# FPGA_POWER_AND_CONFIGURATION.net
KiCad netlist of a schematic drawn in Altium Designer
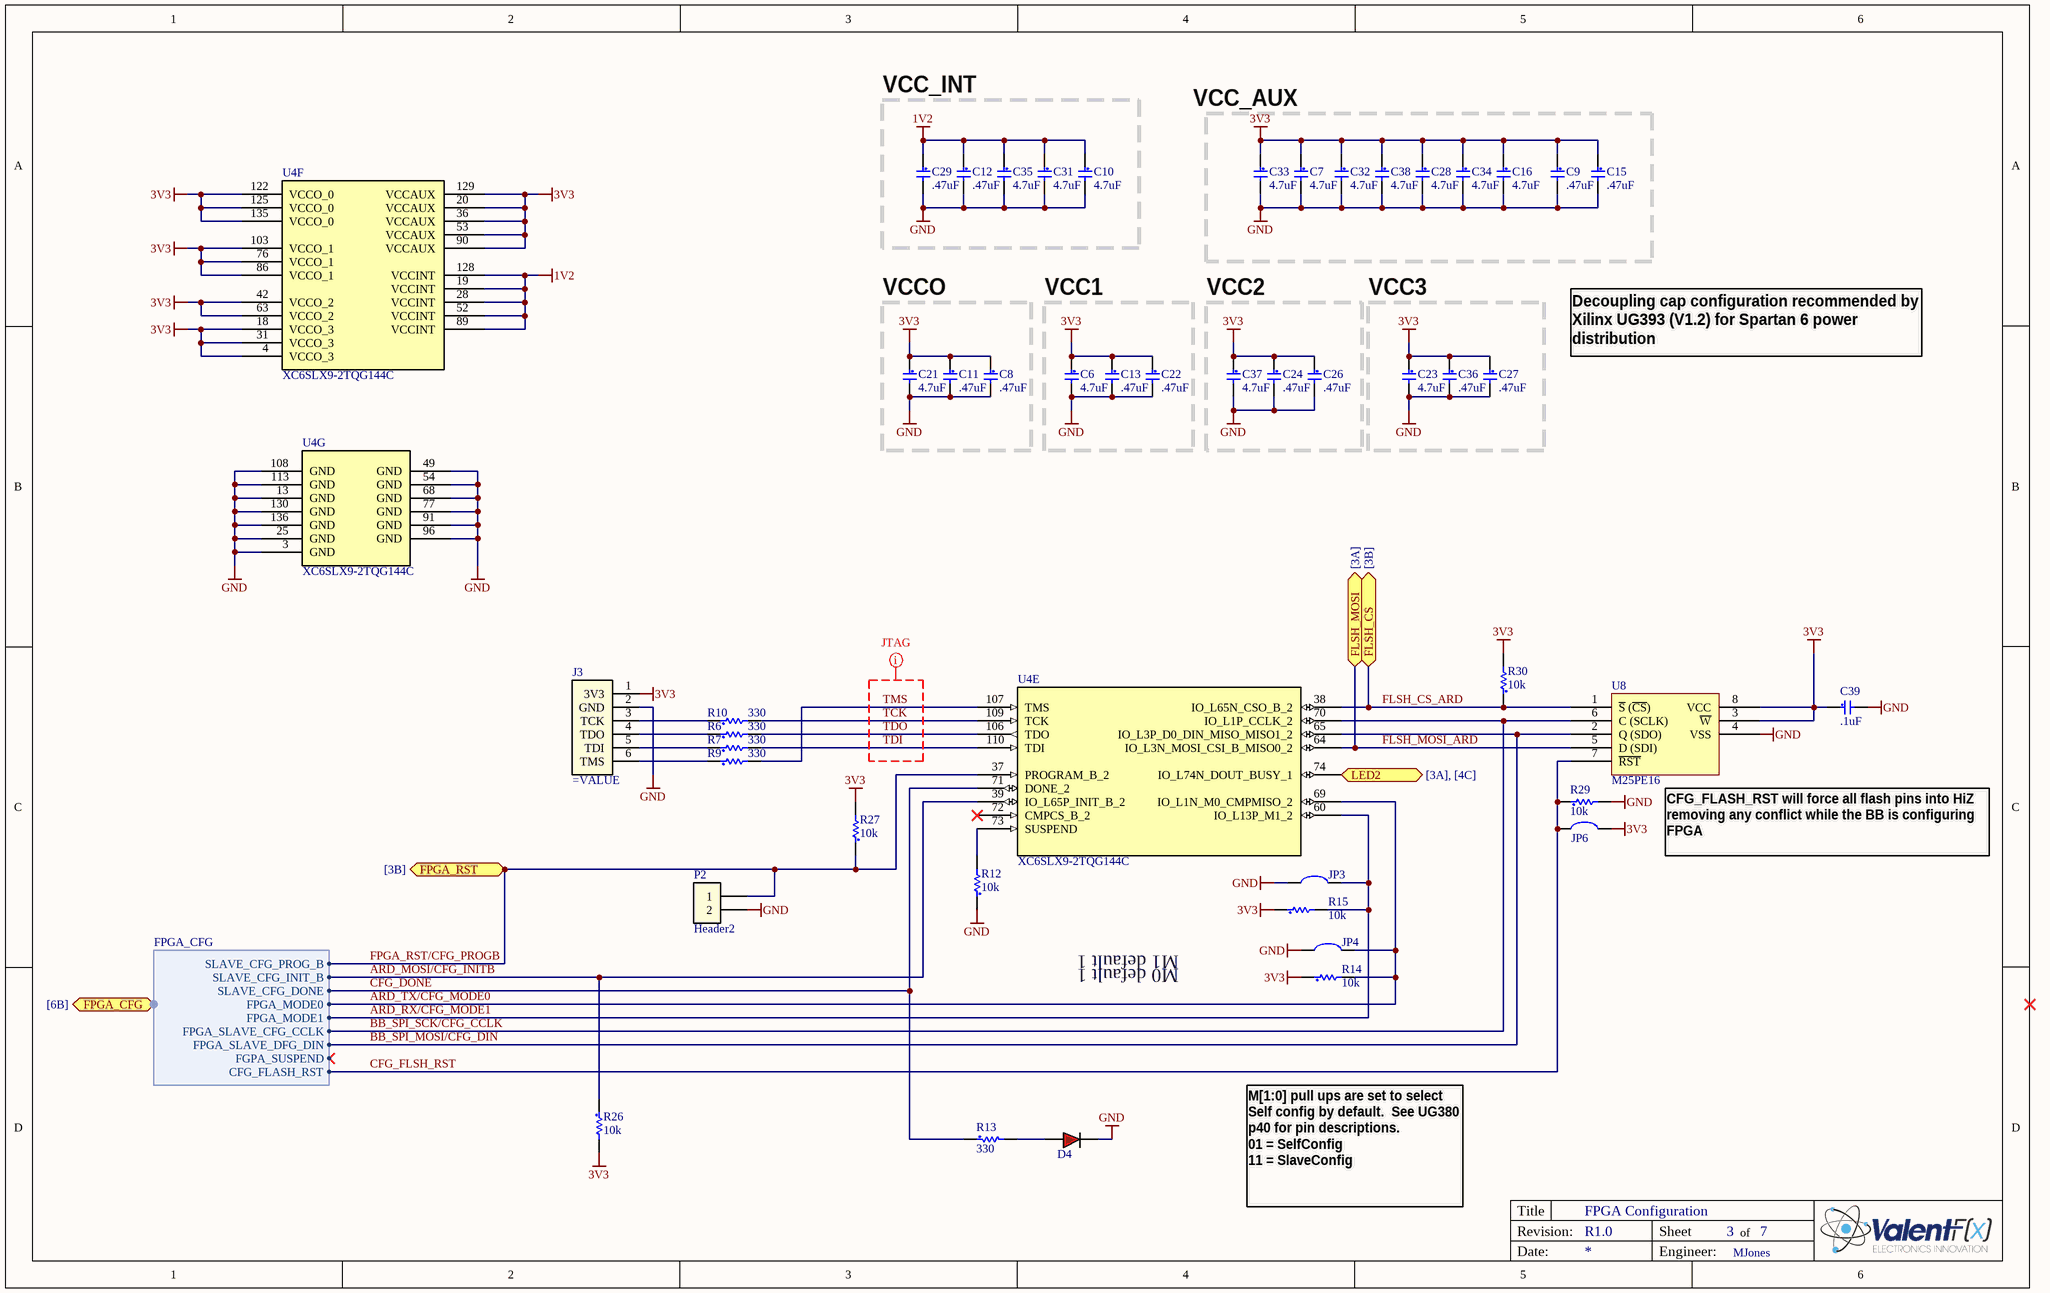
[diagram p0: FPGA_POWER_AND_CONFIGURATION.SchDoc]

(export (version "E")
  (design (tool "Eeschema 10.0.6"))
  (components
    (comp (ref "C6")
      (value "4.7uF")
      (footprint "C0603 - Marked")
      (description "4.7uF 6.3volts X5R 10% (MLCC) - SMD/SMT 0603")
      (fields
        (field (name "MANUFACTURER") "Murata Electronics North America")
        (field (name "MANUFACTURER PART NUMBER") "GRM188R60J475KE19D")
      )
      (libsource (lib "mCapacitors") (part "C0603 - GRM188R60J475KE19D"))
    )
    (comp (ref "C7")
      (value "4.7uF")
      (footprint "C0603 - Marked")
      (description "4.7uF 6.3volts X5R 10% (MLCC) - SMD/SMT 0603")
      (fields
        (field (name "MANUFACTURER") "Murata Electronics North America")
        (field (name "MANUFACTURER PART NUMBER") "GRM188R60J475KE19D")
      )
      (libsource (lib "mCapacitors") (part "C0603 - GRM188R60J475KE19D"))
    )
    (comp (ref "C8")
      (value ".47uF")
      (footprint "mRCL:C0603")
      (description ".47uF 25VDC X7R 10% SMD 0603 Paper T/R CERAMIC")
      (fields
        (field (name "MANUFACTURER") "Murata Electronics North America")
        (field (name "MANUFACTURER PART NUMBER") "GCM188R71E474KA64D")
      )
      (libsource (lib "mCapacitors") (part "C0603 - GCM188R71E474KA64D"))
    )
    (comp (ref "C9")
      (value ".47uF")
      (footprint "mRCL:C0603")
      (description ".47uF 25VDC X7R 10% SMD 0603 Paper T/R CERAMIC")
      (fields
        (field (name "MANUFACTURER") "Murata Electronics North America")
        (field (name "MANUFACTURER PART NUMBER") "GCM188R71E474KA64D")
      )
      (libsource (lib "mCapacitors") (part "C0603 - GCM188R71E474KA64D"))
    )
    (comp (ref "C10")
      (value "4.7uF")
      (footprint "C0603 - Marked")
      (description "4.7uF 6.3volts X5R 10% (MLCC) - SMD/SMT 0603")
      (fields
        (field (name "MANUFACTURER") "Murata Electronics North America")
        (field (name "MANUFACTURER PART NUMBER") "GRM188R60J475KE19D")
      )
      (libsource (lib "mCapacitors") (part "C0603 - GRM188R60J475KE19D"))
    )
    (comp (ref "C11")
      (value ".47uF")
      (footprint "mRCL:C0603")
      (description ".47uF 25VDC X7R 10% SMD 0603 Paper T/R CERAMIC")
      (fields
        (field (name "MANUFACTURER") "Murata Electronics North America")
        (field (name "MANUFACTURER PART NUMBER") "GCM188R71E474KA64D")
      )
      (libsource (lib "mCapacitors") (part "C0603 - GCM188R71E474KA64D"))
    )
    (comp (ref "C12")
      (value ".47uF")
      (footprint "mRCL:C0603")
      (description ".47uF 25VDC X7R 10% SMD 0603 Paper T/R CERAMIC")
      (fields
        (field (name "MANUFACTURER") "Murata Electronics North America")
        (field (name "MANUFACTURER PART NUMBER") "GCM188R71E474KA64D")
      )
      (libsource (lib "mCapacitors") (part "C0603 - GCM188R71E474KA64D"))
    )
    (comp (ref "C13")
      (value ".47uF")
      (footprint "mRCL:C0603")
      (description ".47uF 25VDC X7R 10% SMD 0603 Paper T/R CERAMIC")
      (fields
        (field (name "MANUFACTURER") "Murata Electronics North America")
        (field (name "MANUFACTURER PART NUMBER") "GCM188R71E474KA64D")
      )
      (libsource (lib "mCapacitors") (part "C0603 - GCM188R71E474KA64D"))
    )
    (comp (ref "C15")
      (value ".47uF")
      (footprint "mRCL:C0603")
      (description ".47uF 25VDC X7R 10% SMD 0603 Paper T/R CERAMIC")
      (fields
        (field (name "MANUFACTURER") "Murata Electronics North America")
        (field (name "MANUFACTURER PART NUMBER") "GCM188R71E474KA64D")
      )
      (libsource (lib "mCapacitors") (part "C0603 - GCM188R71E474KA64D"))
    )
    (comp (ref "C16")
      (value "4.7uF")
      (footprint "C0603 - Marked")
      (description "4.7uF 6.3volts X5R 10% (MLCC) - SMD/SMT 0603")
      (fields
        (field (name "MANUFACTURER") "Murata Electronics North America")
        (field (name "MANUFACTURER PART NUMBER") "GRM188R60J475KE19D")
      )
      (libsource (lib "mCapacitors") (part "C0603 - GRM188R60J475KE19D"))
    )
    (comp (ref "C21")
      (value "4.7uF")
      (footprint "C0603 - Marked")
      (description "4.7uF 6.3volts X5R 10% (MLCC) - SMD/SMT 0603")
      (fields
        (field (name "MANUFACTURER") "Murata Electronics North America")
        (field (name "MANUFACTURER PART NUMBER") "GRM188R60J475KE19D")
      )
      (libsource (lib "mCapacitors") (part "C0603 - GRM188R60J475KE19D"))
    )
    (comp (ref "C22")
      (value ".47uF")
      (footprint "mRCL:C0603")
      (description ".47uF 25VDC X7R 10% SMD 0603 Paper T/R CERAMIC")
      (fields
        (field (name "MANUFACTURER") "Murata Electronics North America")
        (field (name "MANUFACTURER PART NUMBER") "GCM188R71E474KA64D")
      )
      (libsource (lib "mCapacitors") (part "C0603 - GCM188R71E474KA64D"))
    )
    (comp (ref "C23")
      (value "4.7uF")
      (footprint "C0603 - Marked")
      (description "4.7uF 6.3volts X5R 10% (MLCC) - SMD/SMT 0603")
      (fields
        (field (name "MANUFACTURER") "Murata Electronics North America")
        (field (name "MANUFACTURER PART NUMBER") "GRM188R60J475KE19D")
      )
      (libsource (lib "mCapacitors") (part "C0603 - GRM188R60J475KE19D"))
    )
    (comp (ref "C24")
      (value ".47uF")
      (footprint "mRCL:C0603")
      (description ".47uF 25VDC X7R 10% SMD 0603 Paper T/R CERAMIC")
      (fields
        (field (name "MANUFACTURER") "Murata Electronics North America")
        (field (name "MANUFACTURER PART NUMBER") "GCM188R71E474KA64D")
      )
      (libsource (lib "mCapacitors") (part "C0603 - GCM188R71E474KA64D"))
    )
    (comp (ref "C26")
      (value ".47uF")
      (footprint "mRCL:C0603")
      (description ".47uF 25VDC X7R 10% SMD 0603 Paper T/R CERAMIC")
      (fields
        (field (name "MANUFACTURER") "Murata Electronics North America")
        (field (name "MANUFACTURER PART NUMBER") "GCM188R71E474KA64D")
      )
      (libsource (lib "mCapacitors") (part "C0603 - GCM188R71E474KA64D"))
    )
    (comp (ref "C27")
      (value ".47uF")
      (footprint "mRCL:C0603")
      (description ".47uF 25VDC X7R 10% SMD 0603 Paper T/R CERAMIC")
      (fields
        (field (name "MANUFACTURER") "Murata Electronics North America")
        (field (name "MANUFACTURER PART NUMBER") "GCM188R71E474KA64D")
      )
      (libsource (lib "mCapacitors") (part "C0603 - GCM188R71E474KA64D"))
    )
    (comp (ref "C28")
      (value "4.7uF")
      (footprint "C0603 - Marked")
      (description "4.7uF 6.3volts X5R 10% (MLCC) - SMD/SMT 0603")
      (fields
        (field (name "MANUFACTURER") "Murata Electronics North America")
        (field (name "MANUFACTURER PART NUMBER") "GRM188R60J475KE19D")
      )
      (libsource (lib "mCapacitors") (part "C0603 - GRM188R60J475KE19D"))
    )
    (comp (ref "C29")
      (value ".47uF")
      (footprint "mRCL:C0603")
      (description ".47uF 25VDC X7R 10% SMD 0603 Paper T/R CERAMIC")
      (fields
        (field (name "MANUFACTURER") "Murata Electronics North America")
        (field (name "MANUFACTURER PART NUMBER") "GCM188R71E474KA64D")
      )
      (libsource (lib "mCapacitors") (part "C0603 - GCM188R71E474KA64D"))
    )
    (comp (ref "C31")
      (value "4.7uF")
      (footprint "C0603 - Marked")
      (description "4.7uF 6.3volts X5R 10% (MLCC) - SMD/SMT 0603")
      (fields
        (field (name "MANUFACTURER") "Murata Electronics North America")
        (field (name "MANUFACTURER PART NUMBER") "GRM188R60J475KE19D")
      )
      (libsource (lib "mCapacitors") (part "C0603 - GRM188R60J475KE19D"))
    )
    (comp (ref "C32")
      (value "4.7uF")
      (footprint "C0603 - Marked")
      (description "4.7uF 6.3volts X5R 10% (MLCC) - SMD/SMT 0603")
      (fields
        (field (name "MANUFACTURER") "Murata Electronics North America")
        (field (name "MANUFACTURER PART NUMBER") "GRM188R60J475KE19D")
      )
      (libsource (lib "mCapacitors") (part "C0603 - GRM188R60J475KE19D"))
    )
    (comp (ref "C33")
      (value "4.7uF")
      (footprint "C0603 - Marked")
      (description "4.7uF 6.3volts X5R 10% (MLCC) - SMD/SMT 0603")
      (fields
        (field (name "MANUFACTURER") "Murata Electronics North America")
        (field (name "MANUFACTURER PART NUMBER") "GRM188R60J475KE19D")
      )
      (libsource (lib "mCapacitors") (part "C0603 - GRM188R60J475KE19D"))
    )
    (comp (ref "C34")
      (value "4.7uF")
      (footprint "C0603 - Marked")
      (description "4.7uF 6.3volts X5R 10% (MLCC) - SMD/SMT 0603")
      (fields
        (field (name "MANUFACTURER") "Murata Electronics North America")
        (field (name "MANUFACTURER PART NUMBER") "GRM188R60J475KE19D")
      )
      (libsource (lib "mCapacitors") (part "C0603 - GRM188R60J475KE19D"))
    )
    (comp (ref "C35")
      (value "4.7uF")
      (footprint "C0603 - Marked")
      (description "4.7uF 6.3volts X5R 10% (MLCC) - SMD/SMT 0603")
      (fields
        (field (name "MANUFACTURER") "Murata Electronics North America")
        (field (name "MANUFACTURER PART NUMBER") "GRM188R60J475KE19D")
      )
      (libsource (lib "mCapacitors") (part "C0603 - GRM188R60J475KE19D"))
    )
    (comp (ref "C36")
      (value ".47uF")
      (footprint "mRCL:C0603")
      (description ".47uF 25VDC X7R 10% SMD 0603 Paper T/R CERAMIC")
      (fields
        (field (name "MANUFACTURER") "Murata Electronics North America")
        (field (name "MANUFACTURER PART NUMBER") "GCM188R71E474KA64D")
      )
      (libsource (lib "mCapacitors") (part "C0603 - GCM188R71E474KA64D"))
    )
    (comp (ref "C37")
      (value "4.7uF")
      (footprint "C0603 - Marked")
      (description "4.7uF 6.3volts X5R 10% (MLCC) - SMD/SMT 0603")
      (fields
        (field (name "MANUFACTURER") "Murata Electronics North America")
        (field (name "MANUFACTURER PART NUMBER") "GRM188R60J475KE19D")
      )
      (libsource (lib "mCapacitors") (part "C0603 - GRM188R60J475KE19D"))
    )
    (comp (ref "C38")
      (value "4.7uF")
      (footprint "C0603 - Marked")
      (description "4.7uF 6.3volts X5R 10% (MLCC) - SMD/SMT 0603")
      (fields
        (field (name "MANUFACTURER") "Murata Electronics North America")
        (field (name "MANUFACTURER PART NUMBER") "GRM188R60J475KE19D")
      )
      (libsource (lib "mCapacitors") (part "C0603 - GRM188R60J475KE19D"))
    )
    (comp (ref "C39")
      (value ".1uF")
      (footprint "c0603")
      (description "CAP CER 0.1UF 25V Y5V 0603")
      (fields
        (field (name "MANUFACTURER") "Samsung Electro-Mechanics America, Inc")
        (field (name "MANUFACTURER PART NUMBER") "CL10F104ZA8NNNC")
      )
      (libsource (lib "mCapacitors") (part "C0603 - CL10F104ZA8NNNC"))
    )
    (comp (ref "D4")
      (value "598-8010-107F")
      (footprint "LED_0603 - RED")
      (description "LED ALINGAP RED CLEAR 0603 SMD")
      (fields (field (name "MANUFACTURER") "Dialight"))
      (libsource (lib "mDiode") (part "LED0603 - 598-8010-107F"))
    )
    (comp (ref "J3")
      (value "~")
      (footprint "JTAG - Digilent HS1 RA")
      (description "DIGILENT - 410-205 - PROGRAMMING CABLE, JTAG HS1, USB2")
      (fields
        (field (name "MANUFACTURER") "Samtec")
        (field (name "MANUFACTURER PART NUMBER") "TSW-106-08-G-S-RA")
      )
      (libsource (lib "mConnector") (part "JTAG - Digilent HS1"))
    )
    (comp (ref "JP3")
      (value "Solder Jumper")
      (footprint "SOLDER_JUMPER")
      (description "Solder/Configuration Jumper")
      (fields (field (name "MANUFACTURER") "n/a"))
      (libsource (lib "mConnector") (part "Solder Jumper"))
    )
    (comp (ref "JP4")
      (value "Solder Jumper")
      (footprint "SOLDER_JUMPER")
      (description "Solder/Configuration Jumper")
      (fields (field (name "MANUFACTURER") "n/a"))
      (libsource (lib "mConnector") (part "Solder Jumper"))
    )
    (comp (ref "JP6")
      (value "Solder Jumper")
      (footprint "SOLDER_JUMPER")
      (description "Solder/Configuration Jumper")
      (fields (field (name "MANUFACTURER") "n/a"))
      (libsource (lib "mConnector") (part "Solder Jumper"))
    )
    (comp (ref "P2")
      (value "Header2")
      (footprint "HEADER_2_40_100 THRU SIP")
      (description "Header 2 pin")
      (libsource (lib "mConnector") (part "Header2"))
    )
    (comp (ref "R6")
      (value "330")
      (footprint "R0603")
      (description "Thick Film Resistors - SMD 0603 330ohms 5% Tol")
      (fields
        (field (name "MANUFACTURER") "Panasonic")
        (field (name "MANUFACTURER PART NUMBER") "ERJ-3GEYJ331V")
      )
      (libsource (lib "mResistors") (part "R0603 - ERJ-3GEYJ331V"))
    )
    (comp (ref "R7")
      (value "330")
      (footprint "R0603")
      (description "Thick Film Resistors - SMD 0603 330ohms 5% Tol")
      (fields
        (field (name "MANUFACTURER") "Panasonic")
        (field (name "MANUFACTURER PART NUMBER") "ERJ-3GEYJ331V")
      )
      (libsource (lib "mResistors") (part "R0603 - ERJ-3GEYJ331V"))
    )
    (comp (ref "R9")
      (value "330")
      (footprint "R0603")
      (description "Thick Film Resistors - SMD 0603 330ohms 5% Tol")
      (fields
        (field (name "MANUFACTURER") "Panasonic")
        (field (name "MANUFACTURER PART NUMBER") "ERJ-3GEYJ331V")
      )
      (libsource (lib "mResistors") (part "R0603 - ERJ-3GEYJ331V"))
    )
    (comp (ref "R10")
      (value "330")
      (footprint "R0603")
      (description "Thick Film Resistors - SMD 0603 330ohms 5% Tol")
      (fields
        (field (name "MANUFACTURER") "Panasonic")
        (field (name "MANUFACTURER PART NUMBER") "ERJ-3GEYJ331V")
      )
      (libsource (lib "mResistors") (part "R0603 - ERJ-3GEYJ331V"))
    )
    (comp (ref "R12")
      (value "10k")
      (footprint "mRCL:R0603")
      (description "10k Thick Film Resistors - SMD 1/10watt 10Kohms 1%")
      (fields
        (field (name "MANUFACTURER") "Vishay Dale")
        (field (name "MANUFACTURER PART NUMBER") "CRCW060310K0FKEA")
      )
      (libsource (lib "mResistors") (part "R0603 - CRCW060310K0FKEA"))
    )
    (comp (ref "R13")
      (value "330")
      (footprint "R0603")
      (description "Thick Film Resistors - SMD 0603 330ohms 5% Tol")
      (fields
        (field (name "MANUFACTURER") "Panasonic")
        (field (name "MANUFACTURER PART NUMBER") "ERJ-3GEYJ331V")
      )
      (libsource (lib "") (part "R0603 - ERJ-3GEYJ331V_1"))
    )
    (comp (ref "R14")
      (value "10k")
      (footprint "mRCL:R0603")
      (description "10k Thick Film Resistors - SMD 1/10watt 10Kohms 1%")
      (fields
        (field (name "MANUFACTURER") "Vishay Dale")
        (field (name "MANUFACTURER PART NUMBER") "CRCW060310K0FKEA")
      )
      (libsource (lib "mResistors") (part "R0603 - CRCW060310K0FKEA"))
    )
    (comp (ref "R15")
      (value "10k")
      (footprint "mRCL:R0603")
      (description "10k Thick Film Resistors - SMD 1/10watt 10Kohms 1%")
      (fields
        (field (name "MANUFACTURER") "Vishay Dale")
        (field (name "MANUFACTURER PART NUMBER") "CRCW060310K0FKEA")
      )
      (libsource (lib "mResistors") (part "R0603 - CRCW060310K0FKEA"))
    )
    (comp (ref "R26")
      (value "10k")
      (footprint "mRCL:R0603")
      (description "10k Thick Film Resistors - SMD 1/10watt 10Kohms 1%")
      (fields
        (field (name "MANUFACTURER") "Vishay Dale")
        (field (name "MANUFACTURER PART NUMBER") "CRCW060310K0FKEA")
      )
      (libsource (lib "mResistors") (part "R0603 - CRCW060310K0FKEA"))
    )
    (comp (ref "R27")
      (value "10k")
      (footprint "mRCL:R0603")
      (description "10k Thick Film Resistors - SMD 1/10watt 10Kohms 1%")
      (fields
        (field (name "MANUFACTURER") "Vishay Dale")
        (field (name "MANUFACTURER PART NUMBER") "CRCW060310K0FKEA")
      )
      (libsource (lib "mResistors") (part "R0603 - CRCW060310K0FKEA"))
    )
    (comp (ref "R29")
      (value "10k")
      (footprint "mRCL:R0603")
      (description "10k Thick Film Resistors - SMD 1/10watt 10Kohms 1%")
      (fields
        (field (name "MANUFACTURER") "Vishay Dale")
        (field (name "MANUFACTURER PART NUMBER") "CRCW060310K0FKEA")
      )
      (libsource (lib "mResistors") (part "R0603 - CRCW060310K0FKEA"))
    )
    (comp (ref "R30")
      (value "10k")
      (footprint "mRCL:R0603")
      (description "10k Thick Film Resistors - SMD 1/10watt 10Kohms 1%")
      (fields
        (field (name "MANUFACTURER") "Vishay Dale")
        (field (name "MANUFACTURER PART NUMBER") "CRCW060310K0FKEA")
      )
      (libsource (lib "mResistors") (part "R0603 - CRCW060310K0FKEA"))
    )
    (comp (ref "U4")
      (value "XC6SLX9-2TQG144C")
      (footprint "TQ144_L")
      (description "IC FPAG SPARTAN 6 9K 144TQFP")
      (fields (field (name "MANUFACTURER") "Xilinx Inc"))
      (libsource (lib "mIC") (part "FPGA - XC6SLX9-2TQG144C"))
    )
    (comp (ref "U8")
      (value "M25PE16")
      (footprint "SOIC127P830X200-8L")
      (description "IC FLASH 16MBIT 75MHZ 8SOIC")
      (fields
        (field (name "MANUFACTURER") "Numonyx/ST Micro")
        (field (name "MANUFACTURER PART NUMBER") "M25PE16-VMW6TG")
      )
      (libsource (lib "ICs") (part "M25PE16-VMW6TG"))
    )
  )
  (nets
    (net (code "2") (name "/ARD_MOSI{slash}CFG_INITB") (class "Default")
      (node (ref "R26") (pin "1") (pinfunction "1_1") (pintype "passive"))
      (node (ref "U4") (pin "39") (pinfunction "IO_L65P_INIT_B_2_39") (pintype "bidirectional"))
    )
    (net (code "3") (name "/ARD_RX{slash}CFG_MODE1") (class "Default")
      (node (ref "JP3") (pin "1") (pinfunction "1_1") (pintype "passive"))
      (node (ref "R15") (pin "2") (pinfunction "2_2") (pintype "passive"))
      (node (ref "U4") (pin "60") (pinfunction "IO_L13P_M1_2_60") (pintype "bidirectional"))
    )
    (net (code "4") (name "/ARD_TX{slash}CFG_MODE0") (class "Default")
      (node (ref "JP4") (pin "1") (pinfunction "1_1") (pintype "passive"))
      (node (ref "R14") (pin "2") (pinfunction "2_2") (pintype "passive"))
      (node (ref "U4") (pin "69") (pinfunction "IO_L1N_M0_CMPMISO_2_69") (pintype "bidirectional"))
    )
    (net (code "5") (name "/BB_SPI_MOSI{slash}CFG_DIN") (class "Default")
      (node (ref "U4") (pin "65") (pinfunction "IO_L3P_D0_DIN_MISO_MISO1_2_65") (pintype "bidirectional"))
      (node (ref "U8") (pin "2") (pinfunction "Q_(SDO)_2") (pintype "passive"))
    )
    (net (code "6") (name "/BB_SPI_SCK{slash}CFG_CCLK") (class "Default")
      (node (ref "U4") (pin "70") (pinfunction "IO_L1P_CCLK_2_70") (pintype "bidirectional"))
      (node (ref "U8") (pin "6") (pinfunction "C_(SCLK)_6") (pintype "passive"))
    )
    (net (code "7") (name "/CFG_DONE") (class "Default")
      (node (ref "R13") (pin "1") (pinfunction "1_1") (pintype "passive"))
      (node (ref "U4") (pin "71") (pinfunction "DONE_2_71") (pintype "bidirectional"))
    )
    (net (code "8") (name "/CFG_FLSH_RST") (class "Default")
      (node (ref "JP6") (pin "2") (pinfunction "2_2") (pintype "passive"))
      (node (ref "R29") (pin "1") (pinfunction "1_1") (pintype "passive"))
      (node (ref "U8") (pin "7") (pinfunction "~{RST}_7") (pintype "passive"))
    )
    (net (code "9") (name "/FLSH_CS_ARD") (class "Default")
      (node (ref "R30") (pin "1") (pinfunction "1_1") (pintype "passive"))
      (node (ref "U4") (pin "38") (pinfunction "IO_L65N_CSO_B_2_38") (pintype "bidirectional"))
      (node (ref "U8") (pin "1") (pinfunction "~{S}_(~{CS})_1") (pintype "passive"))
    )
    (net (code "10") (name "/FLSH_MOSI_ARD") (class "Default")
      (node (ref "U4") (pin "64") (pinfunction "IO_L3N_MOSI_CSI_B_MISO0_2_64") (pintype "bidirectional"))
      (node (ref "U8") (pin "5") (pinfunction "D_(SDI)_5") (pintype "passive"))
    )
    (net (code "11") (name "/FPGA_RST{slash}CFG_PROGB") (class "Default")
      (node (ref "P2") (pin "1") (pinfunction "1_1") (pintype "passive"))
      (node (ref "R27") (pin "1") (pinfunction "1_1") (pintype "passive"))
      (node (ref "U4") (pin "37") (pinfunction "PROGRAM_B_2_37") (pintype "input"))
    )
    (net (code "12") (name "/LED2") (class "Default")
      (node (ref "U4") (pin "74") (pinfunction "IO_L74N_DOUT_BUSY_1_74") (pintype "bidirectional"))
    )
    (net (code "13") (name "/TCK") (class "Default")
      (node (ref "R10") (pin "2") (pinfunction "2_2") (pintype "passive"))
      (node (ref "U4") (pin "109") (pinfunction "TCK_109") (pintype "input"))
    )
    (net (code "14") (name "/TDI") (class "Default")
      (node (ref "R7") (pin "2") (pinfunction "2_2") (pintype "passive"))
      (node (ref "U4") (pin "110") (pinfunction "TDI_110") (pintype "input"))
    )
    (net (code "15") (name "/TDO") (class "Default")
      (node (ref "R6") (pin "2") (pinfunction "2_2") (pintype "passive"))
      (node (ref "U4") (pin "106") (pinfunction "TDO_106") (pintype "output"))
    )
    (net (code "16") (name "/TMS") (class "Default")
      (node (ref "R9") (pin "2") (pinfunction "2_2") (pintype "passive"))
      (node (ref "U4") (pin "107") (pinfunction "TMS_107") (pintype "input"))
    )
    (net (code "18") (name "1V2") (class "Default")
      (node (ref "C10") (pin "1") (pinfunction "1_1") (pintype "passive"))
      (node (ref "C12") (pin "1") (pinfunction "1_1") (pintype "passive"))
      (node (ref "C29") (pin "1") (pinfunction "1_1") (pintype "passive"))
      (node (ref "C31") (pin "1") (pinfunction "1_1") (pintype "passive"))
      (node (ref "C35") (pin "1") (pinfunction "1_1") (pintype "passive"))
      (node (ref "U4") (pin "128") (pinfunction "VCCINT_128") (pintype "power_in"))
      (node (ref "U4") (pin "19") (pinfunction "VCCINT_19") (pintype "power_in"))
      (node (ref "U4") (pin "28") (pinfunction "VCCINT_28") (pintype "power_in"))
      (node (ref "U4") (pin "52") (pinfunction "VCCINT_52") (pintype "power_in"))
      (node (ref "U4") (pin "89") (pinfunction "VCCINT_89") (pintype "power_in"))
    )
    (net (code "19") (name "3V3") (class "Default")
      (node (ref "C11") (pin "1") (pinfunction "1_1") (pintype "passive"))
      (node (ref "C13") (pin "1") (pinfunction "1_1") (pintype "passive"))
      (node (ref "C15") (pin "1") (pinfunction "1_1") (pintype "passive"))
      (node (ref "C16") (pin "1") (pinfunction "1_1") (pintype "passive"))
      (node (ref "C21") (pin "1") (pinfunction "1_1") (pintype "passive"))
      (node (ref "C22") (pin "1") (pinfunction "1_1") (pintype "passive"))
      (node (ref "C23") (pin "1") (pinfunction "1_1") (pintype "passive"))
      (node (ref "C24") (pin "1") (pinfunction "1_1") (pintype "passive"))
      (node (ref "C26") (pin "1") (pinfunction "1_1") (pintype "passive"))
      (node (ref "C27") (pin "1") (pinfunction "1_1") (pintype "passive"))
      (node (ref "C28") (pin "1") (pinfunction "1_1") (pintype "passive"))
      (node (ref "C32") (pin "1") (pinfunction "1_1") (pintype "passive"))
      (node (ref "C33") (pin "1") (pinfunction "1_1") (pintype "passive"))
      (node (ref "C34") (pin "1") (pinfunction "1_1") (pintype "passive"))
      (node (ref "C36") (pin "1") (pinfunction "1_1") (pintype "passive"))
      (node (ref "C37") (pin "1") (pinfunction "1_1") (pintype "passive"))
      (node (ref "C38") (pin "1") (pinfunction "1_1") (pintype "passive"))
      (node (ref "C39") (pin "1") (pinfunction "1_1") (pintype "passive"))
      (node (ref "C6") (pin "1") (pinfunction "1_1") (pintype "passive"))
      (node (ref "C7") (pin "1") (pinfunction "1_1") (pintype "passive"))
      (node (ref "C8") (pin "1") (pinfunction "1_1") (pintype "passive"))
      (node (ref "C9") (pin "1") (pinfunction "1_1") (pintype "passive"))
      (node (ref "J3") (pin "1") (pinfunction "3V3_1") (pintype "passive"))
      (node (ref "JP6") (pin "1") (pinfunction "1_1") (pintype "passive"))
      (node (ref "R14") (pin "1") (pinfunction "1_1") (pintype "passive"))
      (node (ref "R15") (pin "1") (pinfunction "1_1") (pintype "passive"))
      (node (ref "R26") (pin "2") (pinfunction "2_2") (pintype "passive"))
      (node (ref "R27") (pin "2") (pinfunction "2_2") (pintype "passive"))
      (node (ref "R30") (pin "2") (pinfunction "2_2") (pintype "passive"))
      (node (ref "U4") (pin "103") (pinfunction "VCCO_1_103") (pintype "power_in"))
      (node (ref "U4") (pin "122") (pinfunction "VCCO_0_122") (pintype "power_in"))
      (node (ref "U4") (pin "125") (pinfunction "VCCO_0_125") (pintype "power_in"))
      (node (ref "U4") (pin "129") (pinfunction "VCCAUX_129") (pintype "power_in"))
      (node (ref "U4") (pin "135") (pinfunction "VCCO_0_135") (pintype "power_in"))
      (node (ref "U4") (pin "18") (pinfunction "VCCO_3_18") (pintype "power_in"))
      (node (ref "U4") (pin "20") (pinfunction "VCCAUX_20") (pintype "power_in"))
      (node (ref "U4") (pin "31") (pinfunction "VCCO_3_31") (pintype "power_in"))
      (node (ref "U4") (pin "36") (pinfunction "VCCAUX_36") (pintype "power_in"))
      (node (ref "U4") (pin "4") (pinfunction "VCCO_3_4") (pintype "power_in"))
      (node (ref "U4") (pin "42") (pinfunction "VCCO_2_42") (pintype "power_in"))
      (node (ref "U4") (pin "53") (pinfunction "VCCAUX_53") (pintype "power_in"))
      (node (ref "U4") (pin "63") (pinfunction "VCCO_2_63") (pintype "power_in"))
      (node (ref "U4") (pin "76") (pinfunction "VCCO_1_76") (pintype "power_in"))
      (node (ref "U4") (pin "86") (pinfunction "VCCO_1_86") (pintype "power_in"))
      (node (ref "U4") (pin "90") (pinfunction "VCCAUX_90") (pintype "power_in"))
      (node (ref "U8") (pin "3") (pinfunction "~{W}_3") (pintype "passive"))
      (node (ref "U8") (pin "8") (pinfunction "VCC_8") (pintype "passive"))
    )
    (net (code "20") (name "GND") (class "Default")
      (node (ref "C10") (pin "2") (pinfunction "2_2") (pintype "passive"))
      (node (ref "C11") (pin "2") (pinfunction "2_2") (pintype "passive"))
      (node (ref "C12") (pin "2") (pinfunction "2_2") (pintype "passive"))
      (node (ref "C13") (pin "2") (pinfunction "2_2") (pintype "passive"))
      (node (ref "C15") (pin "2") (pinfunction "2_2") (pintype "passive"))
      (node (ref "C16") (pin "2") (pinfunction "2_2") (pintype "passive"))
      (node (ref "C21") (pin "2") (pinfunction "2_2") (pintype "passive"))
      (node (ref "C22") (pin "2") (pinfunction "2_2") (pintype "passive"))
      (node (ref "C23") (pin "2") (pinfunction "2_2") (pintype "passive"))
      (node (ref "C24") (pin "2") (pinfunction "2_2") (pintype "passive"))
      (node (ref "C26") (pin "2") (pinfunction "2_2") (pintype "passive"))
      (node (ref "C27") (pin "2") (pinfunction "2_2") (pintype "passive"))
      (node (ref "C28") (pin "2") (pinfunction "2_2") (pintype "passive"))
      (node (ref "C29") (pin "2") (pinfunction "2_2") (pintype "passive"))
      (node (ref "C31") (pin "2") (pinfunction "2_2") (pintype "passive"))
      (node (ref "C32") (pin "2") (pinfunction "2_2") (pintype "passive"))
      (node (ref "C33") (pin "2") (pinfunction "2_2") (pintype "passive"))
      (node (ref "C34") (pin "2") (pinfunction "2_2") (pintype "passive"))
      (node (ref "C35") (pin "2") (pinfunction "2_2") (pintype "passive"))
      (node (ref "C36") (pin "2") (pinfunction "2_2") (pintype "passive"))
      (node (ref "C37") (pin "2") (pinfunction "2_2") (pintype "passive"))
      (node (ref "C38") (pin "2") (pinfunction "2_2") (pintype "passive"))
      (node (ref "C39") (pin "2") (pinfunction "2_2") (pintype "passive"))
      (node (ref "C6") (pin "2") (pinfunction "2_2") (pintype "passive"))
      (node (ref "C7") (pin "2") (pinfunction "2_2") (pintype "passive"))
      (node (ref "C8") (pin "2") (pinfunction "2_2") (pintype "passive"))
      (node (ref "C9") (pin "2") (pinfunction "2_2") (pintype "passive"))
      (node (ref "D4") (pin "C") (pinfunction "C_C") (pintype "passive"))
      (node (ref "J3") (pin "2") (pinfunction "GND_2") (pintype "passive"))
      (node (ref "JP3") (pin "2") (pinfunction "2_2") (pintype "passive"))
      (node (ref "JP4") (pin "2") (pinfunction "2_2") (pintype "passive"))
      (node (ref "P2") (pin "2") (pinfunction "2_2") (pintype "passive"))
      (node (ref "R12") (pin "1") (pinfunction "1_1") (pintype "passive"))
      (node (ref "R29") (pin "2") (pinfunction "2_2") (pintype "passive"))
      (node (ref "U4") (pin "108") (pinfunction "GND_108") (pintype "power_in"))
      (node (ref "U4") (pin "113") (pinfunction "GND_113") (pintype "power_in"))
      (node (ref "U4") (pin "13") (pinfunction "GND_13") (pintype "power_in"))
      (node (ref "U4") (pin "130") (pinfunction "GND_130") (pintype "power_in"))
      (node (ref "U4") (pin "136") (pinfunction "GND_136") (pintype "power_in"))
      (node (ref "U4") (pin "25") (pinfunction "GND_25") (pintype "power_in"))
      (node (ref "U4") (pin "3") (pinfunction "GND_3") (pintype "power_in"))
      (node (ref "U4") (pin "49") (pinfunction "GND_49") (pintype "power_in"))
      (node (ref "U4") (pin "54") (pinfunction "GND_54") (pintype "power_in"))
      (node (ref "U4") (pin "68") (pinfunction "GND_68") (pintype "power_in"))
      (node (ref "U4") (pin "77") (pinfunction "GND_77") (pintype "power_in"))
      (node (ref "U4") (pin "91") (pinfunction "GND_91") (pintype "power_in"))
      (node (ref "U4") (pin "96") (pinfunction "GND_96") (pintype "power_in"))
      (node (ref "U8") (pin "4") (pinfunction "VSS_4") (pintype "passive"))
    )
    (net (code "21") (name "Net-(D4-PadA)") (class "Default")
      (node (ref "D4") (pin "A") (pinfunction "A_A") (pintype "passive"))
      (node (ref "R13") (pin "2") (pinfunction "2_2") (pintype "passive"))
    )
    (net (code "22") (name "Net-(J3-TCK)") (class "Default")
      (node (ref "J3") (pin "3") (pinfunction "TCK_3") (pintype "passive"))
      (node (ref "R10") (pin "1") (pinfunction "1_1") (pintype "passive"))
    )
    (net (code "23") (name "Net-(J3-TDI)") (class "Default")
      (node (ref "J3") (pin "5") (pinfunction "TDI_5") (pintype "passive"))
      (node (ref "R7") (pin "1") (pinfunction "1_1") (pintype "passive"))
    )
    (net (code "24") (name "Net-(J3-TDO)") (class "Default")
      (node (ref "J3") (pin "4") (pinfunction "TDO_4") (pintype "passive"))
      (node (ref "R6") (pin "1") (pinfunction "1_1") (pintype "passive"))
    )
    (net (code "25") (name "Net-(J3-TMS)") (class "Default")
      (node (ref "J3") (pin "6") (pinfunction "TMS_6") (pintype "passive"))
      (node (ref "R9") (pin "1") (pinfunction "1_1") (pintype "passive"))
    )
    (net (code "26") (name "Net-(U4E-SUSPEND)") (class "Default")
      (node (ref "R12") (pin "2") (pinfunction "2_2") (pintype "passive"))
      (node (ref "U4") (pin "73") (pinfunction "SUSPEND_73") (pintype "input"))
    )
    (net (code "27") (name "unconnected-(U4E-CMPCS_B_2-Pad72)") (class "Default")
      (node (ref "U4") (pin "72") (pinfunction "CMPCS_B_2_72") (pintype "input+no_connect"))
    )
  )
)
